# MovuinoHealthBandV0_2_7_2-max86141-v0_2_.net
KiCad netlist of a schematic drawn in EAGLE
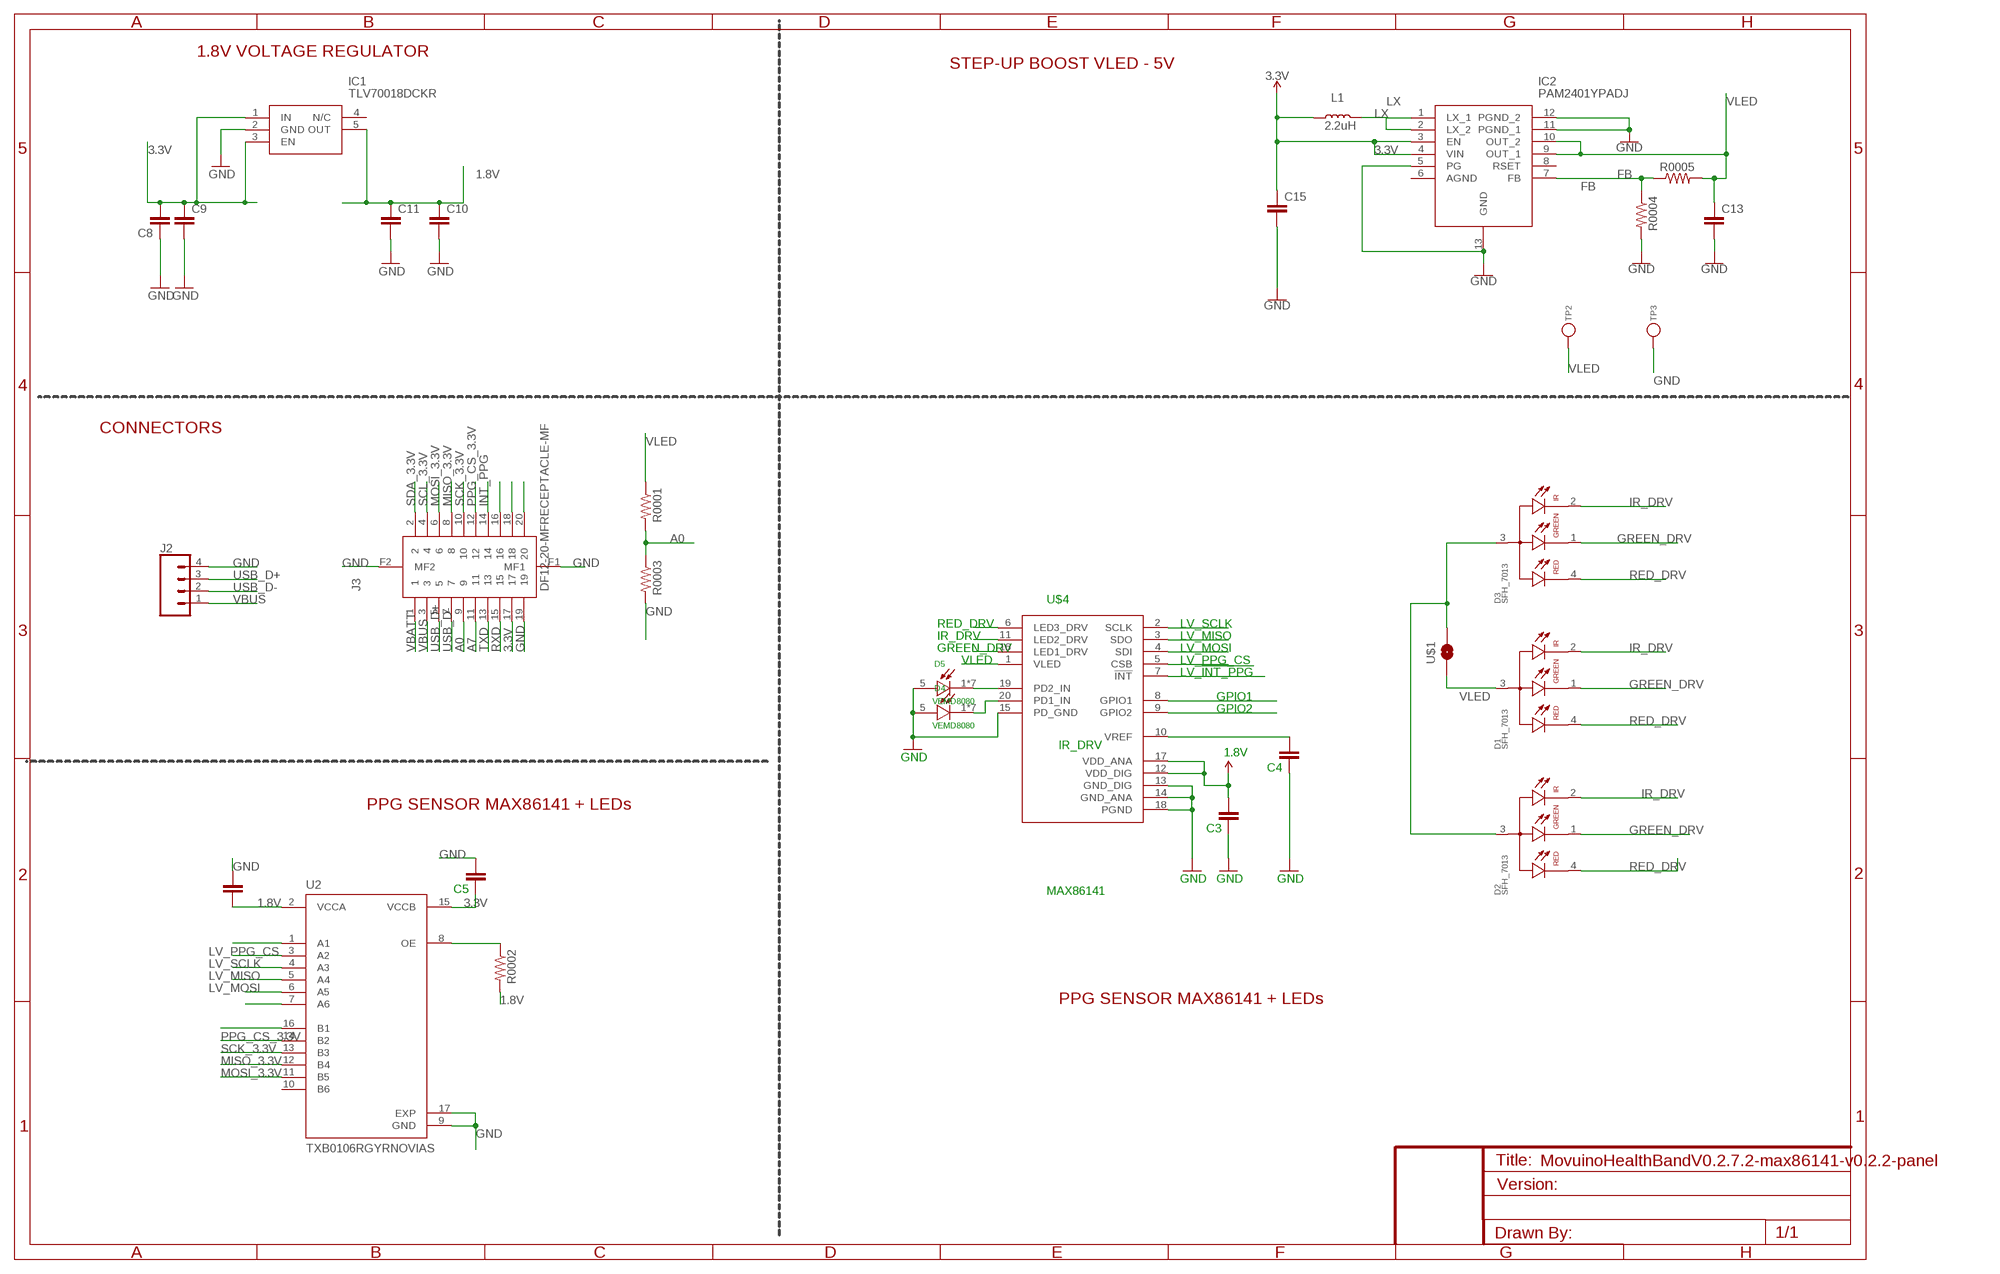
[diagram p0: schematic, sheet 1]

(export (version "E")
  (design (tool "Eeschema 10.0.6"))
  (components
    (comp (ref "C3")
      (value "1uF")
      (footprint "eagle-import:0402-CAP")
      (libsource (lib "eagle-import") (part "CAP0402-CAP"))
    )
    (comp (ref "C4")
      (value "10uF")
      (footprint "eagle-import:0402-CAP")
      (libsource (lib "eagle-import") (part "CAP0402-CAP"))
    )
    (comp (ref "C5")
      (value "0.1uF")
      (footprint "eagle-import:0402-CAP")
      (libsource (lib "eagle-import") (part "CAP0402-CAP"))
    )
    (comp (ref "C6")
      (value "0.1uF")
      (footprint "eagle-import:0402-CAP")
      (libsource (lib "eagle-import") (part "CAP0402-CAP"))
    )
    (comp (ref "C8")
      (value "10uF")
      (footprint "eagle-import:0402-CAP-SMALL-TDOCU")
      (libsource (lib "eagle-import") (part "CAP0402-CAP-SMALL-TDOCU"))
    )
    (comp (ref "C9")
      (value "0.1uF")
      (footprint "eagle-import:0402-CAP-SMALL-TDOCU")
      (libsource (lib "eagle-import") (part "CAP0402-CAP-SMALL-TDOCU"))
    )
    (comp (ref "C10")
      (value "0.1uF")
      (footprint "eagle-import:0402-CAP-SMALL-TDOCU")
      (libsource (lib "eagle-import") (part "CAP0402-CAP-SMALL-TDOCU"))
    )
    (comp (ref "C11")
      (value "4.7uF")
      (footprint "eagle-import:0402-CAP-SMALL-TDOCU")
      (libsource (lib "eagle-import") (part "CAP0402-CAP-SMALL-TDOCU"))
    )
    (comp (ref "C13")
      (value "22uF")
      (footprint "eagle-import:0402-CAP-SMALL-TDOCU")
      (libsource (lib "eagle-import") (part "CAP0402-CAP-SMALL-TDOCU"))
    )
    (comp (ref "C15")
      (value "10uF")
      (footprint "eagle-import:0402-CAP-SMALL-TDOCU")
      (libsource (lib "eagle-import") (part "CAP0402-CAP-SMALL-TDOCU"))
    )
    (comp (ref "D1")
      (value "SFH_7013")
      (footprint "eagle-import:SFH_7013")
      (fields (field (name "MF") "OSRAM Opto") (field (name "MP") "SFH 7013"))
      (libsource (lib "eagle-import") (part "SFH_7013"))
    )
    (comp (ref "D2")
      (value "SFH_7013")
      (footprint "eagle-import:SFH_7013")
      (fields (field (name "MF") "OSRAM Opto") (field (name "MP") "SFH 7013"))
      (libsource (lib "eagle-import") (part "SFH_7013"))
    )
    (comp (ref "D3")
      (value "SFH_7013")
      (footprint "eagle-import:SFH_7013")
      (fields (field (name "MF") "OSRAM Opto") (field (name "MP") "SFH 7013"))
      (libsource (lib "eagle-import") (part "SFH_7013"))
    )
    (comp (ref "D4")
      (value "VEMD8080")
      (footprint "eagle-import:XDCR_VEMD8080")
      (fields (field (name "MF") "Vishay Semiconductor Opto Division"))
      (libsource (lib "eagle-import") (part "VEMD8080"))
    )
    (comp (ref "D5")
      (value "VEMD8080")
      (footprint "eagle-import:XDCR_VEMD8080")
      (fields (field (name "MF") "Vishay Semiconductor Opto Division"))
      (libsource (lib "eagle-import") (part "VEMD8080"))
    )
    (comp (ref "IC1")
      (value "TLV70018DCKR")
      (footprint "eagle-import:SOT65P210X110-5N")
      (fields (field (name "MOUSER_PART_NUMBER") "595-TLV70018DCKR"))
      (libsource (lib "eagle-import") (part "TLV70018DCKR"))
    )
    (comp (ref "IC2")
      (value "PAM2401YPADJ")
      (footprint "eagle-import:SON45P295X295X60-13N")
      (fields (field (name "MOUSER_PART_NUMBER") "621-PAM2401YPADJ"))
      (libsource (lib "eagle-import") (part "PAM2401YPADJ"))
    )
    (comp (ref "J2")
      (value "CONN_04POGO-2.54")
      (footprint "eagle-import:POGO_2.54_X4")
      (libsource (lib "eagle-import") (part "CONN_04POGO-2.54"))
    )
    (comp (ref "J3")
      (value "DF12-20-MFRECEPTACLE-MF")
      (footprint "eagle-import:DF12-20-DS")
      (fields (field (name "MPN") "DF12-20DS-0.5V(86)"))
      (libsource (lib "eagle-import") (part "DF12-20-MFRECEPTACLE-MF"))
    )
    (comp (ref "L1")
      (value "2.2uH")
      (footprint "eagle-import:INDC2016X100N")
      (fields (field (name "MPN") "LQM2MPN2R2MGHL"))
      (libsource (lib "eagle-import") (part "INDUCTOR"))
    )
    (comp (ref "R0001")
      (value "100K")
      (footprint "eagle-import:0402-RES")
      (fields (field (name "TOLERANCE") "1%"))
      (libsource (lib "eagle-import") (part "RESISTOR0402-RES"))
    )
    (comp (ref "R0002")
      (value "100K")
      (footprint "eagle-import:0402-RES")
      (fields (field (name "TOLERANCE") "1%"))
      (libsource (lib "eagle-import") (part "RESISTOR0402-RES"))
    )
    (comp (ref "R0003")
      (value "100K")
      (footprint "eagle-import:0402-RES")
      (fields (field (name "TOLERANCE") "1%"))
      (libsource (lib "eagle-import") (part "RESISTOR0402-RES"))
    )
    (comp (ref "R0004")
      (value "100K")
      (footprint "eagle-import:0402-RES")
      (fields (field (name "TOLERANCE") "1%"))
      (libsource (lib "eagle-import") (part "RESISTOR0402-RES"))
    )
    (comp (ref "R0005")
      (value "750K")
      (footprint "eagle-import:0402-RES")
      (fields (field (name "TOLERANCE") "1%"))
      (libsource (lib "eagle-import") (part "RESISTOR0402-RES"))
    )
    (comp (ref "TP2")
      (value "TESTPOINT1MM-ROUND-CREAM")
      (footprint "eagle-import:TESTPOINT_ROUND_1MM-CREAM")
      (libsource (lib "eagle-import") (part "TESTPOINT1MM-ROUND-CREAM"))
    )
    (comp (ref "TP3")
      (value "TESTPOINT1MM-ROUND-CREAM")
      (footprint "eagle-import:TESTPOINT_ROUND_1MM-CREAM")
      (libsource (lib "eagle-import") (part "TESTPOINT1MM-ROUND-CREAM"))
    )
    (comp (ref "U$1")
      (value "0402-JUMPER")
      (footprint "eagle-import:0402-JUMPER")
      (libsource (lib "eagle-import") (part "0402-JUMPER"))
    )
    (comp (ref "U$4")
      (value "MAX86141")
      (footprint "eagle-import:20_PIN_WLP")
      (libsource (lib "eagle-import") (part "MAX86141"))
    )
    (comp (ref "U2")
      (value "TXB0106RGYRNOVIAS")
      (footprint "eagle-import:QFN50P400X350X100-17N-2")
      (libsource (lib "eagle-import") (part "TXB0106RGYRNOVIAS"))
    )
  )
  (nets
    (net (code "1") (name "/A0") (class "Default")
      (node (ref "J3") (pin "9") (pinfunction "9_9") (pintype "bidirectional"))
      (node (ref "R0001") (pin "2") (pinfunction "2_2") (pintype "passive"))
      (node (ref "R0003") (pin "1") (pinfunction "1_1") (pintype "passive"))
    )
    (net (code "2") (name "/A7") (class "Default")
      (node (ref "J3") (pin "11") (pinfunction "11_11") (pintype "bidirectional"))
    )
    (net (code "3") (name "/FB") (class "Default")
      (node (ref "IC2") (pin "7") (pinfunction "FB_7") (pintype "bidirectional"))
      (node (ref "R0004") (pin "1") (pinfunction "1_1") (pintype "passive"))
      (node (ref "R0005") (pin "1") (pinfunction "1_1") (pintype "passive"))
    )
    (net (code "4") (name "/GPIO1") (class "Default")
      (node (ref "U$4") (pin "8") (pinfunction "GPIO1_8") (pintype "bidirectional"))
    )
    (net (code "5") (name "/GPIO2") (class "Default")
      (node (ref "U$4") (pin "9") (pinfunction "GPIO2_9") (pintype "bidirectional"))
    )
    (net (code "6") (name "/GREEN_DRV") (class "Default")
      (node (ref "D1") (pin "1") (pinfunction "CATHODE_EMITTER_2_1") (pintype "passive"))
      (node (ref "D2") (pin "1") (pinfunction "CATHODE_EMITTER_2_1") (pintype "passive"))
      (node (ref "D3") (pin "1") (pinfunction "CATHODE_EMITTER_2_1") (pintype "passive"))
      (node (ref "U$4") (pin "16") (pinfunction "LED1_DRV_16") (pintype "bidirectional"))
    )
    (net (code "7") (name "/INT_PPG") (class "Default")
      (node (ref "J3") (pin "14") (pinfunction "14_14") (pintype "bidirectional"))
    )
    (net (code "8") (name "/IR_DRV") (class "Default")
      (node (ref "D1") (pin "2") (pinfunction "CATHODE_EMITTER_3_2") (pintype "passive"))
      (node (ref "D2") (pin "2") (pinfunction "CATHODE_EMITTER_3_2") (pintype "passive"))
      (node (ref "D3") (pin "2") (pinfunction "CATHODE_EMITTER_3_2") (pintype "passive"))
      (node (ref "U$4") (pin "11") (pinfunction "LED2_DRV_11") (pintype "bidirectional"))
    )
    (net (code "9") (name "/LV_MISO") (class "Default")
      (node (ref "U$4") (pin "3") (pinfunction "SDO_3") (pintype "bidirectional"))
      (node (ref "U2") (pin "5") (pinfunction "A4_5") (pintype "bidirectional"))
    )
    (net (code "10") (name "/LV_MOSI") (class "Default")
      (node (ref "U$4") (pin "4") (pinfunction "SDI_4") (pintype "bidirectional"))
      (node (ref "U2") (pin "6") (pinfunction "A5_6") (pintype "bidirectional"))
    )
    (net (code "11") (name "/LV_PPG_CS") (class "Default")
      (node (ref "U$4") (pin "5") (pinfunction "CSB_5") (pintype "bidirectional"))
      (node (ref "U2") (pin "3") (pinfunction "A2_3") (pintype "bidirectional"))
    )
    (net (code "12") (name "/LV_SCLK") (class "Default")
      (node (ref "U$4") (pin "2") (pinfunction "SCLK_2") (pintype "bidirectional"))
      (node (ref "U2") (pin "4") (pinfunction "A3_4") (pintype "bidirectional"))
    )
    (net (code "13") (name "/LV_~{INT_PPG}") (class "Default")
      (node (ref "U$4") (pin "7") (pinfunction "~{INT}_7") (pintype "bidirectional"))
    )
    (net (code "14") (name "/LX") (class "Default")
      (node (ref "IC2") (pin "1") (pinfunction "LX_1_1") (pintype "bidirectional"))
      (node (ref "IC2") (pin "2") (pinfunction "LX_2_2") (pintype "bidirectional"))
      (node (ref "L1") (pin "2") (pinfunction "2_2") (pintype "passive"))
    )
    (net (code "15") (name "/MISO_3.3V") (class "Default")
      (node (ref "J3") (pin "8") (pinfunction "8_8") (pintype "bidirectional"))
      (node (ref "U2") (pin "12") (pinfunction "B4_12") (pintype "bidirectional"))
    )
    (net (code "16") (name "/MOSI_3.3V") (class "Default")
      (node (ref "J3") (pin "6") (pinfunction "6_6") (pintype "bidirectional"))
      (node (ref "U2") (pin "11") (pinfunction "B5_11") (pintype "bidirectional"))
    )
    (net (code "17") (name "/PPG_CS_3.3V") (class "Default")
      (node (ref "J3") (pin "12") (pinfunction "12_12") (pintype "bidirectional"))
      (node (ref "U2") (pin "14") (pinfunction "B2_14") (pintype "bidirectional"))
    )
    (net (code "18") (name "/RED_DRV") (class "Default")
      (node (ref "D1") (pin "4") (pinfunction "CATHODE_EMITTER_1_4") (pintype "passive"))
      (node (ref "D2") (pin "4") (pinfunction "CATHODE_EMITTER_1_4") (pintype "passive"))
      (node (ref "D3") (pin "4") (pinfunction "CATHODE_EMITTER_1_4") (pintype "passive"))
      (node (ref "U$4") (pin "6") (pinfunction "LED3_DRV_6") (pintype "bidirectional"))
    )
    (net (code "19") (name "/RXD") (class "Default")
      (node (ref "J3") (pin "15") (pinfunction "15_15") (pintype "bidirectional"))
    )
    (net (code "20") (name "/SCK_3.3V") (class "Default")
      (node (ref "J3") (pin "10") (pinfunction "10_10") (pintype "bidirectional"))
      (node (ref "U2") (pin "13") (pinfunction "B3_13") (pintype "bidirectional"))
    )
    (net (code "21") (name "/SCL_3.3V") (class "Default")
      (node (ref "J3") (pin "4") (pinfunction "4_4") (pintype "bidirectional"))
    )
    (net (code "22") (name "/SDA_3.3V") (class "Default")
      (node (ref "J3") (pin "2") (pinfunction "2_2") (pintype "bidirectional"))
    )
    (net (code "23") (name "/TXD") (class "Default")
      (node (ref "J3") (pin "13") (pinfunction "13_13") (pintype "bidirectional"))
    )
    (net (code "24") (name "/USB_D+") (class "Default")
      (node (ref "J2") (pin "3") (pinfunction "3_3") (pintype "passive"))
      (node (ref "J3") (pin "5") (pinfunction "5_5") (pintype "bidirectional"))
    )
    (net (code "25") (name "/USB_D-") (class "Default")
      (node (ref "J2") (pin "2") (pinfunction "2_2") (pintype "passive"))
      (node (ref "J3") (pin "7") (pinfunction "7_7") (pintype "bidirectional"))
    )
    (net (code "26") (name "/VBATT") (class "Default")
      (node (ref "J3") (pin "1") (pinfunction "1_1") (pintype "bidirectional"))
    )
    (net (code "27") (name "/VBUS") (class "Default")
      (node (ref "J2") (pin "1") (pinfunction "1_1") (pintype "passive"))
      (node (ref "J3") (pin "3") (pinfunction "3_3") (pintype "bidirectional"))
    )
    (net (code "28") (name "/VLED") (class "Default")
      (node (ref "C13") (pin "1") (pinfunction "1_1") (pintype "passive"))
      (node (ref "D1") (pin "3") (pinfunction "ANODE_EMITTER_1/2/3_3") (pintype "passive"))
      (node (ref "IC2") (pin "10") (pinfunction "OUT_2_10") (pintype "bidirectional"))
      (node (ref "IC2") (pin "9") (pinfunction "OUT_1_9") (pintype "bidirectional"))
      (node (ref "R0001") (pin "1") (pinfunction "1_1") (pintype "passive"))
      (node (ref "R0005") (pin "2") (pinfunction "2_2") (pintype "passive"))
      (node (ref "TP2") (pin "P$1") (pinfunction "P$1_P$1") (pintype "bidirectional"))
      (node (ref "U$1") (pin "1") (pinfunction "1_1") (pintype "bidirectional"))
      (node (ref "U$4") (pin "1") (pinfunction "VLED_1") (pintype "bidirectional"))
    )
    (net (code "29") (name "1.8V") (class "Default")
      (node (ref "C10") (pin "1") (pinfunction "1_1") (pintype "passive"))
      (node (ref "C11") (pin "1") (pinfunction "1_1") (pintype "passive"))
      (node (ref "C3") (pin "2") (pinfunction "2_2") (pintype "passive"))
      (node (ref "C6") (pin "1") (pinfunction "1_1") (pintype "passive"))
      (node (ref "IC1") (pin "5") (pinfunction "OUT_5") (pintype "bidirectional"))
      (node (ref "R0002") (pin "2") (pinfunction "2_2") (pintype "passive"))
      (node (ref "U$4") (pin "12") (pinfunction "VDD_DIG_12") (pintype "bidirectional"))
      (node (ref "U$4") (pin "17") (pinfunction "VDD_ANA_17") (pintype "bidirectional"))
      (node (ref "U2") (pin "2") (pinfunction "VCCA_2") (pintype "power_in"))
    )
    (net (code "30") (name "3.3V") (class "Default")
      (node (ref "C15") (pin "1") (pinfunction "1_1") (pintype "passive"))
      (node (ref "C5") (pin "1") (pinfunction "1_1") (pintype "passive"))
      (node (ref "C8") (pin "2") (pinfunction "2_2") (pintype "passive"))
      (node (ref "C9") (pin "1") (pinfunction "1_1") (pintype "passive"))
      (node (ref "IC1") (pin "1") (pinfunction "IN_1") (pintype "bidirectional"))
      (node (ref "IC1") (pin "3") (pinfunction "EN_3") (pintype "bidirectional"))
      (node (ref "IC2") (pin "3") (pinfunction "EN_3") (pintype "bidirectional"))
      (node (ref "IC2") (pin "4") (pinfunction "VIN_4") (pintype "bidirectional"))
      (node (ref "J3") (pin "17") (pinfunction "17_17") (pintype "bidirectional"))
      (node (ref "L1") (pin "1") (pinfunction "1_1") (pintype "passive"))
      (node (ref "U2") (pin "15") (pinfunction "VCCB_15") (pintype "power_in"))
    )
    (net (code "31") (name "GND") (class "Default")
      (node (ref "C10") (pin "2") (pinfunction "2_2") (pintype "passive"))
      (node (ref "C11") (pin "2") (pinfunction "2_2") (pintype "passive"))
      (node (ref "C13") (pin "2") (pinfunction "2_2") (pintype "passive"))
      (node (ref "C15") (pin "2") (pinfunction "2_2") (pintype "passive"))
      (node (ref "C3") (pin "1") (pinfunction "1_1") (pintype "passive"))
      (node (ref "C4") (pin "1") (pinfunction "1_1") (pintype "passive"))
      (node (ref "C5") (pin "2") (pinfunction "2_2") (pintype "passive"))
      (node (ref "C6") (pin "2") (pinfunction "2_2") (pintype "passive"))
      (node (ref "C8") (pin "1") (pinfunction "1_1") (pintype "passive"))
      (node (ref "C9") (pin "2") (pinfunction "2_2") (pintype "passive"))
      (node (ref "D4") (pin "5") (pinfunction "A_5") (pintype "passive"))
      (node (ref "D5") (pin "5") (pinfunction "A_5") (pintype "passive"))
      (node (ref "IC1") (pin "2") (pinfunction "GND_2") (pintype "bidirectional"))
      (node (ref "IC2") (pin "11") (pinfunction "PGND_1_11") (pintype "bidirectional"))
      (node (ref "IC2") (pin "12") (pinfunction "PGND_2_12") (pintype "bidirectional"))
      (node (ref "IC2") (pin "13") (pinfunction "GND_13") (pintype "bidirectional"))
      (node (ref "IC2") (pin "5") (pinfunction "PG_5") (pintype "bidirectional"))
      (node (ref "J2") (pin "4") (pinfunction "4_4") (pintype "passive"))
      (node (ref "J3") (pin "19") (pinfunction "19_19") (pintype "bidirectional"))
      (node (ref "J3") (pin "F1") (pinfunction "MF1_F1") (pintype "bidirectional"))
      (node (ref "J3") (pin "F2") (pinfunction "MF2_F2") (pintype "bidirectional"))
      (node (ref "R0003") (pin "2") (pinfunction "2_2") (pintype "passive"))
      (node (ref "R0004") (pin "2") (pinfunction "2_2") (pintype "passive"))
      (node (ref "TP3") (pin "P$1") (pinfunction "P$1_P$1") (pintype "bidirectional"))
      (node (ref "U$4") (pin "13") (pinfunction "GND_DIG_13") (pintype "bidirectional"))
      (node (ref "U$4") (pin "14") (pinfunction "GND_ANA_14") (pintype "bidirectional"))
      (node (ref "U$4") (pin "15") (pinfunction "PD_GND_15") (pintype "bidirectional"))
      (node (ref "U$4") (pin "18") (pinfunction "PGND_18") (pintype "bidirectional"))
      (node (ref "U2") (pin "17") (pinfunction "EXP_17") (pintype "passive"))
      (node (ref "U2") (pin "9") (pinfunction "GND_9") (pintype "power_in"))
    )
    (net (code "32") (name "Net-(D2-ANODE_EMITTER_1{slash}2{slash}3)") (class "Default")
      (node (ref "D2") (pin "3") (pinfunction "ANODE_EMITTER_1/2/3_3") (pintype "passive"))
      (node (ref "D3") (pin "3") (pinfunction "ANODE_EMITTER_1/2/3_3") (pintype "passive"))
      (node (ref "U$1") (pin "2") (pinfunction "2_2") (pintype "bidirectional"))
    )
    (net (code "33") (name "Net-(U$4-PD1_IN)") (class "Default")
      (node (ref "D4") (pin "1") (pinfunction "C_1") (pintype "passive"))
      (node (ref "D4") (pin "2") (pinfunction "C_2") (pintype "passive"))
      (node (ref "D4") (pin "3") (pinfunction "C_3") (pintype "passive"))
      (node (ref "D4") (pin "4") (pinfunction "C_4") (pintype "passive"))
      (node (ref "D4") (pin "6") (pinfunction "C_6") (pintype "passive"))
      (node (ref "D4") (pin "7") (pinfunction "C_7") (pintype "passive"))
      (node (ref "D4") (pin "8") (pinfunction "C_8") (pintype "passive"))
      (node (ref "U$4") (pin "20") (pinfunction "PD1_IN_20") (pintype "bidirectional"))
    )
    (net (code "34") (name "Net-(U$4-PD2_IN)") (class "Default")
      (node (ref "D5") (pin "1") (pinfunction "C_1") (pintype "passive"))
      (node (ref "D5") (pin "2") (pinfunction "C_2") (pintype "passive"))
      (node (ref "D5") (pin "3") (pinfunction "C_3") (pintype "passive"))
      (node (ref "D5") (pin "4") (pinfunction "C_4") (pintype "passive"))
      (node (ref "D5") (pin "6") (pinfunction "C_6") (pintype "passive"))
      (node (ref "D5") (pin "7") (pinfunction "C_7") (pintype "passive"))
      (node (ref "D5") (pin "8") (pinfunction "C_8") (pintype "passive"))
      (node (ref "U$4") (pin "19") (pinfunction "PD2_IN_19") (pintype "bidirectional"))
    )
    (net (code "35") (name "Net-(U$4-VREF)") (class "Default")
      (node (ref "C4") (pin "2") (pinfunction "2_2") (pintype "passive"))
      (node (ref "U$4") (pin "10") (pinfunction "VREF_10") (pintype "bidirectional"))
    )
    (net (code "36") (name "Net-(U2-OE)") (class "Default")
      (node (ref "R0002") (pin "1") (pinfunction "1_1") (pintype "passive"))
      (node (ref "U2") (pin "8") (pinfunction "OE_8") (pintype "output"))
    )
    (net (code "37") (name "unconnected-(IC1-N{slash}C-Pad4)") (class "Default")
      (node (ref "IC1") (pin "4") (pinfunction "N/C_4") (pintype "no_connect"))
    )
    (net (code "38") (name "unconnected-(IC2-AGND-Pad6)") (class "Default")
      (node (ref "IC2") (pin "6") (pinfunction "AGND_6") (pintype "bidirectional"))
    )
    (net (code "39") (name "unconnected-(IC2-RSET-Pad8)") (class "Default")
      (node (ref "IC2") (pin "8") (pinfunction "RSET_8") (pintype "bidirectional"))
    )
    (net (code "40") (name "unconnected-(J3-Pad16)") (class "Default")
      (node (ref "J3") (pin "16") (pinfunction "16_16") (pintype "bidirectional"))
    )
    (net (code "41") (name "unconnected-(J3-Pad18)") (class "Default")
      (node (ref "J3") (pin "18") (pinfunction "18_18") (pintype "bidirectional"))
    )
    (net (code "42") (name "unconnected-(J3-Pad20)") (class "Default")
      (node (ref "J3") (pin "20") (pinfunction "20_20") (pintype "bidirectional"))
    )
    (net (code "43") (name "unconnected-(U2-A1-Pad1)") (class "Default")
      (node (ref "U2") (pin "1") (pinfunction "A1_1") (pintype "bidirectional"))
    )
    (net (code "44") (name "unconnected-(U2-A6-Pad7)") (class "Default")
      (node (ref "U2") (pin "7") (pinfunction "A6_7") (pintype "bidirectional"))
    )
    (net (code "45") (name "unconnected-(U2-B1-Pad16)") (class "Default")
      (node (ref "U2") (pin "16") (pinfunction "B1_16") (pintype "bidirectional"))
    )
    (net (code "46") (name "unconnected-(U2-B6-Pad10)") (class "Default")
      (node (ref "U2") (pin "10") (pinfunction "B6_10") (pintype "bidirectional"))
    )
  )
)
